# Strain_gauge.net
KiCad netlist of a schematic drawn in EAGLE
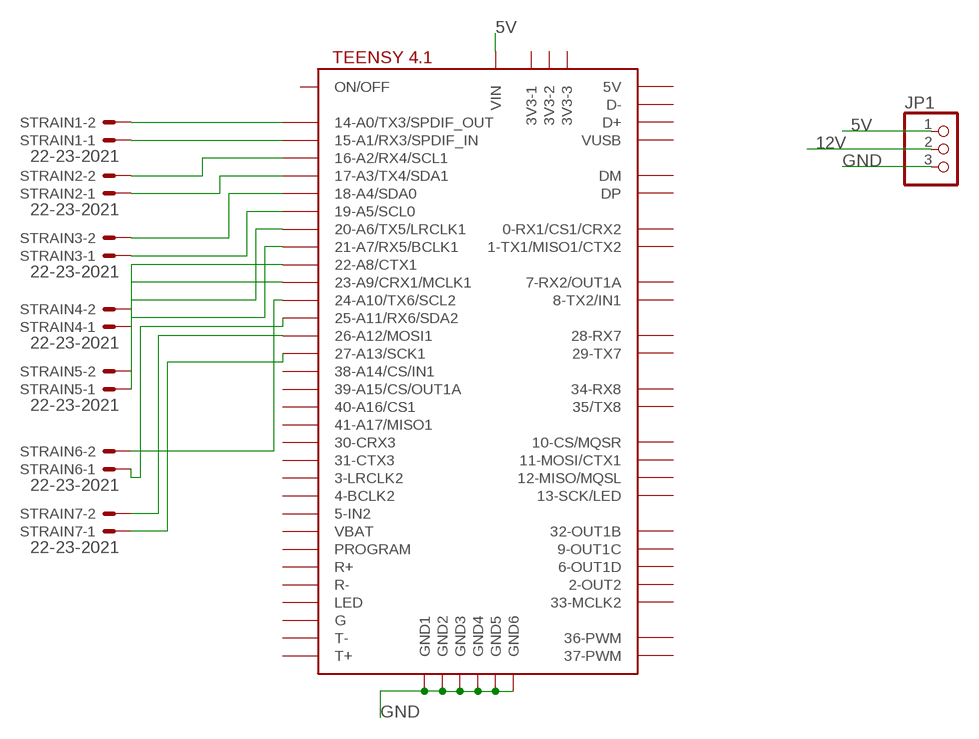
[diagram p0: schematic, sheet 1]

(export (version "E")
  (design (tool "Eeschema 10.0.6"))
  (components
    (comp (ref "JP1")
      (value "PINHD-1X3")
      (footprint "eagle-import:1X03")
      (libsource (lib "eagle-import") (part "PINHD-1X3"))
    )
    (comp (ref "STRAIN1")
      (value "22-23-2021")
      (footprint "eagle-import:22-23-2021")
      (fields (field (name "MF") "MOLEX"))
      (libsource (lib "eagle-import") (part "22-23-2021"))
    )
    (comp (ref "STRAIN2")
      (value "22-23-2021")
      (footprint "eagle-import:22-23-2021")
      (fields (field (name "MF") "MOLEX"))
      (libsource (lib "eagle-import") (part "22-23-2021"))
    )
    (comp (ref "STRAIN3")
      (value "22-23-2021")
      (footprint "eagle-import:22-23-2021")
      (fields (field (name "MF") "MOLEX"))
      (libsource (lib "eagle-import") (part "22-23-2021"))
    )
    (comp (ref "STRAIN4")
      (value "22-23-2021")
      (footprint "eagle-import:22-23-2021")
      (fields (field (name "MF") "MOLEX"))
      (libsource (lib "eagle-import") (part "22-23-2021"))
    )
    (comp (ref "STRAIN5")
      (value "22-23-2021")
      (footprint "eagle-import:22-23-2021")
      (fields (field (name "MF") "MOLEX"))
      (libsource (lib "eagle-import") (part "22-23-2021"))
    )
    (comp (ref "STRAIN6")
      (value "22-23-2021")
      (footprint "eagle-import:22-23-2021")
      (fields (field (name "MF") "MOLEX"))
      (libsource (lib "eagle-import") (part "22-23-2021"))
    )
    (comp (ref "STRAIN7")
      (value "22-23-2021")
      (footprint "eagle-import:22-23-2021")
      (fields (field (name "MF") "MOLEX"))
      (libsource (lib "eagle-import") (part "22-23-2021"))
    )
    (comp (ref "U$1")
      (value "TEENSY41")
      (footprint "eagle-import:TEENSY41")
      (libsource (lib "eagle-import") (part "TEENSY41"))
    )
  )
  (nets
    (net (code "1") (name "/5V") (class "Default")
      (node (ref "JP1") (pin "1") (pinfunction "1_1") (pintype "passive"))
      (node (ref "U$1") (pin "VIN") (pinfunction "VIN_VIN") (pintype "bidirectional"))
    )
    (net (code "2") (name "/12V") (class "Default")
      (node (ref "JP1") (pin "2") (pinfunction "2_2") (pintype "passive"))
    )
    (net (code "3") (name "/GND") (class "Default")
      (node (ref "JP1") (pin "3") (pinfunction "3_3") (pintype "passive"))
      (node (ref "U$1") (pin "GND1") (pinfunction "GND1_GND1") (pintype "bidirectional"))
      (node (ref "U$1") (pin "GND2") (pinfunction "GND2_GND2") (pintype "bidirectional"))
      (node (ref "U$1") (pin "GND3") (pinfunction "GND3_GND3") (pintype "bidirectional"))
      (node (ref "U$1") (pin "GND4") (pinfunction "GND4_GND4") (pintype "bidirectional"))
      (node (ref "U$1") (pin "GND5") (pinfunction "GND5_GND5") (pintype "bidirectional"))
      (node (ref "U$1") (pin "GND6") (pinfunction "GND6_GND6") (pintype "bidirectional"))
    )
    (net (code "4") (name "Net-(STRAIN1A-S)") (class "Default")
      (node (ref "STRAIN1") (pin "1") (pinfunction "S_1") (pintype "passive"))
      (node (ref "U$1") (pin "15-A1/RX3/SPDIF_IN") (pinfunction "15-A1/RX3/SPDIF_IN_15-A1/RX3/SPDIF_IN") (pintype "bidirectional"))
    )
    (net (code "5") (name "Net-(STRAIN1B-S)") (class "Default")
      (node (ref "STRAIN1") (pin "2") (pinfunction "S_2") (pintype "passive"))
      (node (ref "U$1") (pin "14-A0/TX3/SPDIF_OUT") (pinfunction "14-A0/TX3/SPDIF_OUT_14-A0/TX3/SPDIF_OUT") (pintype "bidirectional"))
    )
    (net (code "6") (name "Net-(STRAIN2A-S)") (class "Default")
      (node (ref "STRAIN2") (pin "1") (pinfunction "S_1") (pintype "passive"))
      (node (ref "U$1") (pin "17-A3/TX4/SDA1") (pinfunction "17-A3/TX4/SDA1_17-A3/TX4/SDA1") (pintype "bidirectional"))
    )
    (net (code "7") (name "Net-(STRAIN2B-S)") (class "Default")
      (node (ref "STRAIN2") (pin "2") (pinfunction "S_2") (pintype "passive"))
      (node (ref "U$1") (pin "16-A2/RX4/SCL1") (pinfunction "16-A2/RX4/SCL1_16-A2/RX4/SCL1") (pintype "bidirectional"))
    )
    (net (code "8") (name "Net-(STRAIN3A-S)") (class "Default")
      (node (ref "STRAIN3") (pin "1") (pinfunction "S_1") (pintype "passive"))
      (node (ref "U$1") (pin "19-A5/SCL0") (pinfunction "19-A5/SCL0_19-A5/SCL0") (pintype "bidirectional"))
    )
    (net (code "9") (name "Net-(STRAIN3B-S)") (class "Default")
      (node (ref "STRAIN3") (pin "2") (pinfunction "S_2") (pintype "passive"))
      (node (ref "U$1") (pin "18-A4/SDA0") (pinfunction "18-A4/SDA0_18-A4/SDA0") (pintype "bidirectional"))
    )
    (net (code "10") (name "Net-(STRAIN4A-S)") (class "Default")
      (node (ref "STRAIN4") (pin "1") (pinfunction "S_1") (pintype "passive"))
      (node (ref "U$1") (pin "21-A7/RX5/BCLK1") (pinfunction "21-A7/RX5/BCLK1_21-A7/RX5/BCLK1") (pintype "bidirectional"))
    )
    (net (code "11") (name "Net-(STRAIN4B-S)") (class "Default")
      (node (ref "STRAIN4") (pin "2") (pinfunction "S_2") (pintype "passive"))
      (node (ref "U$1") (pin "20-A6/TX5/LRCLK1") (pinfunction "20-A6/TX5/LRCLK1_20-A6/TX5/LRCLK1") (pintype "bidirectional"))
    )
    (net (code "12") (name "Net-(STRAIN5A-S)") (class "Default")
      (node (ref "STRAIN5") (pin "1") (pinfunction "S_1") (pintype "passive"))
      (node (ref "U$1") (pin "23-A9/CRX1/MCLK1") (pinfunction "23-A9/CRX1/MCLK1_23-A9/CRX1/MCLK1") (pintype "bidirectional"))
    )
    (net (code "13") (name "Net-(STRAIN5B-S)") (class "Default")
      (node (ref "STRAIN5") (pin "2") (pinfunction "S_2") (pintype "passive"))
      (node (ref "U$1") (pin "22-A8/CTX1") (pinfunction "22-A8/CTX1_22-A8/CTX1") (pintype "bidirectional"))
    )
    (net (code "14") (name "Net-(STRAIN6A-S)") (class "Default")
      (node (ref "STRAIN6") (pin "1") (pinfunction "S_1") (pintype "passive"))
      (node (ref "U$1") (pin "25-A11/RX6/SDA2") (pinfunction "25-A11/RX6/SDA2_25-A11/RX6/SDA2") (pintype "bidirectional"))
    )
    (net (code "15") (name "Net-(STRAIN6B-S)") (class "Default")
      (node (ref "STRAIN6") (pin "2") (pinfunction "S_2") (pintype "passive"))
      (node (ref "U$1") (pin "24-A10/TX6/SCL2") (pinfunction "24-A10/TX6/SCL2_24-A10/TX6/SCL2") (pintype "bidirectional"))
    )
    (net (code "16") (name "Net-(STRAIN7A-S)") (class "Default")
      (node (ref "STRAIN7") (pin "1") (pinfunction "S_1") (pintype "passive"))
      (node (ref "U$1") (pin "27-A13/SCK1") (pinfunction "27-A13/SCK1_27-A13/SCK1") (pintype "bidirectional"))
    )
    (net (code "17") (name "Net-(STRAIN7B-S)") (class "Default")
      (node (ref "STRAIN7") (pin "2") (pinfunction "S_2") (pintype "passive"))
      (node (ref "U$1") (pin "26-A12/MOSI1") (pinfunction "26-A12/MOSI1_26-A12/MOSI1") (pintype "bidirectional"))
    )
    (net (code "18") (name "unconnected-(U$1-5V-Pad+5V)") (class "Default")
      (node (ref "U$1") (pin "+5V") (pinfunction "5V_+5V") (pintype "bidirectional"))
    )
    (net (code "19") (name "unconnected-(U$1-8-TX2{slash}IN1-Pad8-TX2{slash}IN2)") (class "Default")
      (node (ref "U$1") (pin "8-TX2/IN2") (pinfunction "8-TX2/IN1_8-TX2/IN2") (pintype "bidirectional"))
    )
    (net (code "20") (name "unconnected-(U$1-10-CS{slash}MQSR-Pad10-CS\\MQSR)") (class "Default")
      (node (ref "U$1") (pin "10-CS\\MQSR") (pinfunction "10-CS/MQSR_10-CS\\MQSR") (pintype "bidirectional"))
    )
    (net (code "21") (name "unconnected-(U$1-35{slash}TX8-Pad35-TX8)") (class "Default")
      (node (ref "U$1") (pin "35-TX8") (pinfunction "35/TX8_35-TX8") (pintype "bidirectional"))
    )
    (net (code "22") (name "unconnected-(U$1-Pad0-RX1{slash}CS1{slash}CRX2)") (class "Default")
      (node (ref "U$1") (pin "0-RX1/CS1/CRX2") (pinfunction "0-RX1/CS1/CRX2_0-RX1/CS1/CRX2") (pintype "bidirectional"))
    )
    (net (code "23") (name "unconnected-(U$1-Pad1-TX1{slash}MISO1{slash}CTX2)") (class "Default")
      (node (ref "U$1") (pin "1-TX1/MISO1/CTX2") (pinfunction "1-TX1/MISO1/CTX2_1-TX1/MISO1/CTX2") (pintype "bidirectional"))
    )
    (net (code "24") (name "unconnected-(U$1-Pad2-OUT2)") (class "Default")
      (node (ref "U$1") (pin "2-OUT2") (pinfunction "2-OUT2_2-OUT2") (pintype "bidirectional"))
    )
    (net (code "25") (name "unconnected-(U$1-Pad3-LRCLK2)") (class "Default")
      (node (ref "U$1") (pin "3-LRCLK2") (pinfunction "3-LRCLK2_3-LRCLK2") (pintype "bidirectional"))
    )
    (net (code "26") (name "unconnected-(U$1-Pad3V3-1)") (class "Default")
      (node (ref "U$1") (pin "3V3-1") (pinfunction "3V3-1_3V3-1") (pintype "bidirectional"))
    )
    (net (code "27") (name "unconnected-(U$1-Pad3V3-2)") (class "Default")
      (node (ref "U$1") (pin "3V3-2") (pinfunction "3V3-2_3V3-2") (pintype "bidirectional"))
    )
    (net (code "28") (name "unconnected-(U$1-Pad3V3-3)") (class "Default")
      (node (ref "U$1") (pin "3V3-3") (pinfunction "3V3-3_3V3-3") (pintype "bidirectional"))
    )
    (net (code "29") (name "unconnected-(U$1-Pad4-BCLK2)") (class "Default")
      (node (ref "U$1") (pin "4-BCLK2") (pinfunction "4-BCLK2_4-BCLK2") (pintype "bidirectional"))
    )
    (net (code "30") (name "unconnected-(U$1-Pad5-IN2)") (class "Default")
      (node (ref "U$1") (pin "5-IN2") (pinfunction "5-IN2_5-IN2") (pintype "bidirectional"))
    )
    (net (code "31") (name "unconnected-(U$1-Pad6-OUT1D)") (class "Default")
      (node (ref "U$1") (pin "6-OUT1D") (pinfunction "6-OUT1D_6-OUT1D") (pintype "bidirectional"))
    )
    (net (code "32") (name "unconnected-(U$1-Pad7-RX2{slash}OUT1A)") (class "Default")
      (node (ref "U$1") (pin "7-RX2/OUT1A") (pinfunction "7-RX2/OUT1A_7-RX2/OUT1A") (pintype "bidirectional"))
    )
    (net (code "33") (name "unconnected-(U$1-Pad9-OUT1C)") (class "Default")
      (node (ref "U$1") (pin "9-OUT1C") (pinfunction "9-OUT1C_9-OUT1C") (pintype "bidirectional"))
    )
    (net (code "34") (name "unconnected-(U$1-Pad11-MOSI{slash}CTX1)") (class "Default")
      (node (ref "U$1") (pin "11-MOSI/CTX1") (pinfunction "11-MOSI/CTX1_11-MOSI/CTX1") (pintype "bidirectional"))
    )
    (net (code "35") (name "unconnected-(U$1-Pad12-MISO{slash}MQSL)") (class "Default")
      (node (ref "U$1") (pin "12-MISO/MQSL") (pinfunction "12-MISO/MQSL_12-MISO/MQSL") (pintype "bidirectional"))
    )
    (net (code "36") (name "unconnected-(U$1-Pad13-SCK{slash}LED)") (class "Default")
      (node (ref "U$1") (pin "13-SCK/LED") (pinfunction "13-SCK/LED_13-SCK/LED") (pintype "bidirectional"))
    )
    (net (code "37") (name "unconnected-(U$1-Pad28-RX7)") (class "Default")
      (node (ref "U$1") (pin "28-RX7") (pinfunction "28-RX7_28-RX7") (pintype "bidirectional"))
    )
    (net (code "38") (name "unconnected-(U$1-Pad29-TX7)") (class "Default")
      (node (ref "U$1") (pin "29-TX7") (pinfunction "29-TX7_29-TX7") (pintype "bidirectional"))
    )
    (net (code "39") (name "unconnected-(U$1-Pad30-CRX3)") (class "Default")
      (node (ref "U$1") (pin "30-CRX3") (pinfunction "30-CRX3_30-CRX3") (pintype "bidirectional"))
    )
    (net (code "40") (name "unconnected-(U$1-Pad31-CTX3)") (class "Default")
      (node (ref "U$1") (pin "31-CTX3") (pinfunction "31-CTX3_31-CTX3") (pintype "bidirectional"))
    )
    (net (code "41") (name "unconnected-(U$1-Pad32-OUT1B)") (class "Default")
      (node (ref "U$1") (pin "32-OUT1B") (pinfunction "32-OUT1B_32-OUT1B") (pintype "bidirectional"))
    )
    (net (code "42") (name "unconnected-(U$1-Pad33-MCLK2)") (class "Default")
      (node (ref "U$1") (pin "33-MCLK2") (pinfunction "33-MCLK2_33-MCLK2") (pintype "bidirectional"))
    )
    (net (code "43") (name "unconnected-(U$1-Pad34-RX8)") (class "Default")
      (node (ref "U$1") (pin "34-RX8") (pinfunction "34-RX8_34-RX8") (pintype "bidirectional"))
    )
    (net (code "44") (name "unconnected-(U$1-Pad36-PWM)") (class "Default")
      (node (ref "U$1") (pin "36-PWM") (pinfunction "36-PWM_36-PWM") (pintype "bidirectional"))
    )
    (net (code "45") (name "unconnected-(U$1-Pad37-PWM)") (class "Default")
      (node (ref "U$1") (pin "37-PWM") (pinfunction "37-PWM_37-PWM") (pintype "bidirectional"))
    )
    (net (code "46") (name "unconnected-(U$1-Pad38-A14{slash}CS{slash}IN1)") (class "Default")
      (node (ref "U$1") (pin "38-A14/CS/IN1") (pinfunction "38-A14/CS/IN1_38-A14/CS/IN1") (pintype "bidirectional"))
    )
    (net (code "47") (name "unconnected-(U$1-Pad39-A15{slash}CS{slash}OUT1A)") (class "Default")
      (node (ref "U$1") (pin "39-A15/CS/OUT1A") (pinfunction "39-A15/CS/OUT1A_39-A15/CS/OUT1A") (pintype "bidirectional"))
    )
    (net (code "48") (name "unconnected-(U$1-Pad40-A16{slash}CS1)") (class "Default")
      (node (ref "U$1") (pin "40-A16/CS1") (pinfunction "40-A16/CS1_40-A16/CS1") (pintype "bidirectional"))
    )
    (net (code "49") (name "unconnected-(U$1-Pad41-A17{slash}MISO1)") (class "Default")
      (node (ref "U$1") (pin "41-A17/MISO1") (pinfunction "41-A17/MISO1_41-A17/MISO1") (pintype "bidirectional"))
    )
    (net (code "50") (name "unconnected-(U$1-PadD+)") (class "Default")
      (node (ref "U$1") (pin "D+") (pinfunction "D+_D+") (pintype "bidirectional"))
    )
    (net (code "51") (name "unconnected-(U$1-PadD-)") (class "Default")
      (node (ref "U$1") (pin "D-") (pinfunction "D-_D-") (pintype "bidirectional"))
    )
    (net (code "52") (name "unconnected-(U$1-PadDM)") (class "Default")
      (node (ref "U$1") (pin "DM") (pinfunction "DM_DM") (pintype "bidirectional"))
    )
    (net (code "53") (name "unconnected-(U$1-PadDP)") (class "Default")
      (node (ref "U$1") (pin "DP") (pinfunction "DP_DP") (pintype "bidirectional"))
    )
    (net (code "54") (name "unconnected-(U$1-PadG)") (class "Default")
      (node (ref "U$1") (pin "G") (pinfunction "G_G") (pintype "bidirectional"))
    )
    (net (code "55") (name "unconnected-(U$1-PadLED)") (class "Default")
      (node (ref "U$1") (pin "LED") (pinfunction "LED_LED") (pintype "bidirectional"))
    )
    (net (code "56") (name "unconnected-(U$1-PadON{slash}OFF)") (class "Default")
      (node (ref "U$1") (pin "ON/OFF") (pinfunction "ON/OFF_ON/OFF") (pintype "bidirectional"))
    )
    (net (code "57") (name "unconnected-(U$1-PadPROGRAM)") (class "Default")
      (node (ref "U$1") (pin "PROGRAM") (pinfunction "PROGRAM_PROGRAM") (pintype "bidirectional"))
    )
    (net (code "58") (name "unconnected-(U$1-PadR+)") (class "Default")
      (node (ref "U$1") (pin "R+") (pinfunction "R+_R+") (pintype "bidirectional"))
    )
    (net (code "59") (name "unconnected-(U$1-PadR-)") (class "Default")
      (node (ref "U$1") (pin "R-") (pinfunction "R-_R-") (pintype "bidirectional"))
    )
    (net (code "60") (name "unconnected-(U$1-PadT+)") (class "Default")
      (node (ref "U$1") (pin "T+") (pinfunction "T+_T+") (pintype "bidirectional"))
    )
    (net (code "61") (name "unconnected-(U$1-PadT-)") (class "Default")
      (node (ref "U$1") (pin "T-") (pinfunction "T-_T-") (pintype "bidirectional"))
    )
    (net (code "62") (name "unconnected-(U$1-PadVBAT)") (class "Default")
      (node (ref "U$1") (pin "VBAT") (pinfunction "VBAT_VBAT") (pintype "bidirectional"))
    )
    (net (code "63") (name "unconnected-(U$1-PadVUSB)") (class "Default")
      (node (ref "U$1") (pin "VUSB") (pinfunction "VUSB_VUSB") (pintype "bidirectional"))
    )
  )
)
